# DC_DC_4V.net
KiCad netlist of a schematic drawn in Altium Designer
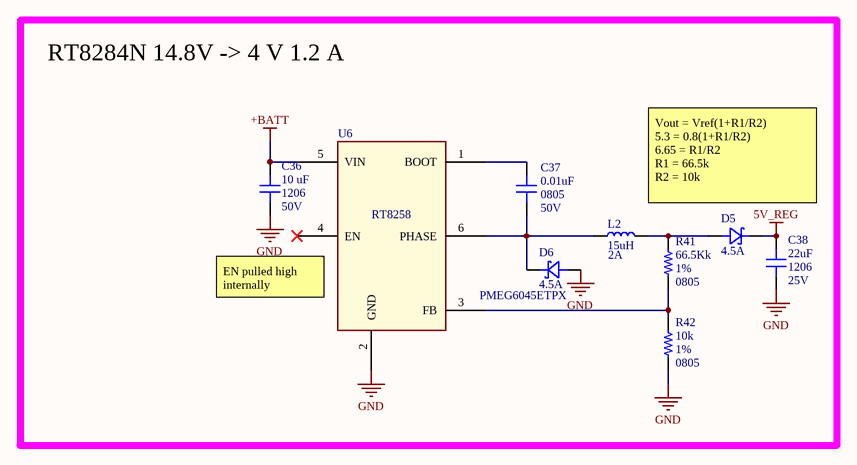
[diagram p0: DC_DC_4V.SchDoc]

(export (version "E")
  (design (tool "Eeschema 10.0.6"))
  (components
    (comp (ref "C36")
      (value "10 uF")
      (footprint "CAP_1206")
      (description "CAP - 1206")
      (fields
        (field (name "PACKAGE") "1206")
        (field (name "VOLTAGE") "50V")
        (field (name "PART NUMBER") "GRT31CR61H106ME01L")
      )
      (libsource (lib "SecureBot") (part "CAP - 1206"))
    )
    (comp (ref "C37")
      (value "0.01uF")
      (footprint "CAP_0805")
      (description "CAP - 0805")
      (fields
        (field (name "PART NUMBER") "CL21B103KBANNNC")
        (field (name "PACKAGE") "0805")
        (field (name "VOLTAGE") "50V")
      )
      (libsource (lib "SecureBot") (part "CAP - 0805"))
    )
    (comp (ref "C38")
      (value "22uF")
      (footprint "CAP_1206")
      (description "CAP - 1206")
      (fields
        (field (name "PART NUMBER") "CL31A226KAHNNNE")
        (field (name "PACKAGE") "1206")
        (field (name "VOLTAGE") "25V")
      )
      (libsource (lib "SecureBot") (part "CAP - 1206"))
    )
    (comp (ref "D5")
      (value "SCHOTTKEY")
      (footprint "DO-214AC_SOD128")
      (fields (field (name "CURRENT") "4.5A") (field (name "PART NUMBER") "PMEG6045ETPX"))
      (libsource (lib "SecureBot") (part "SCHOTTKEY"))
    )
    (comp (ref "D6")
      (value "SCHOTTKEY")
      (footprint "DO-214AC_SOD128")
      (fields (field (name "CURRENT") "4.5A") (field (name "PART NUMBER") "PMEG6045ETPX"))
      (libsource (lib "SecureBot") (part "SCHOTTKEY"))
    )
    (comp (ref "L2")
      (value "15uH")
      (footprint "NR5040T150M")
      (description "IND")
      (fields (field (name "CURRENT") "2A") (field (name "PART NUMBER") "NR5040T150M"))
      (libsource (lib "SecureBot") (part "IND"))
    )
    (comp (ref "R41")
      (value "66.5Kk")
      (footprint "FER_0805")
      (description "RES - 0805")
      (fields
        (field (name "TOLERANCE") "1%")
        (field (name "PACKAGE") "0805")
        (field (name "PART NUMBER") "RC0805FR-0766K5L")
      )
      (libsource (lib "SecureBot") (part "RES - 0805"))
    )
    (comp (ref "R42")
      (value "10k")
      (footprint "FER_0805")
      (description "RES - 0805")
      (fields
        (field (name "TOLERANCE") "1%")
        (field (name "PACKAGE") "0805")
        (field (name "PART NUMBER") "RMCF0805FT10K0")
      )
      (libsource (lib "SecureBot") (part "RES - 0805"))
    )
    (comp (ref "U6") (value "RT8258") (footprint "SOT23-6") (libsource (lib "SecureBot") (part "RT8258")))
  )
  (nets
    (net (code "1") (name "+BATT") (class "Default")
      (node (ref "C36") (pin "1") (pinfunction "1_1") (pintype "passive"))
      (node (ref "U6") (pin "5") (pinfunction "VIN_5") (pintype "passive"))
    )
    (net (code "2") (name "5V_REG") (class "Default")
      (node (ref "C38") (pin "1") (pinfunction "1_1") (pintype "passive"))
      (node (ref "D5") (pin "2") (pinfunction "2_2") (pintype "passive"))
    )
    (net (code "3") (name "GND") (class "Default")
      (node (ref "C36") (pin "2") (pinfunction "2_2") (pintype "passive"))
      (node (ref "C38") (pin "2") (pinfunction "2_2") (pintype "passive"))
      (node (ref "D6") (pin "1") (pinfunction "1_1") (pintype "passive"))
      (node (ref "R42") (pin "2") (pinfunction "2_2") (pintype "passive"))
      (node (ref "U6") (pin "2") (pinfunction "GND_2") (pintype "passive"))
    )
    (net (code "4") (name "Net-(D5-Pad1)") (class "Default")
      (node (ref "D5") (pin "1") (pinfunction "1_1") (pintype "passive"))
      (node (ref "L2") (pin "2") (pinfunction "2_2") (pintype "passive"))
      (node (ref "R41") (pin "1") (pinfunction "1_1") (pintype "passive"))
    )
    (net (code "5") (name "Net-(U6-BOOT)") (class "Default")
      (node (ref "C37") (pin "1") (pinfunction "1_1") (pintype "passive"))
      (node (ref "U6") (pin "1") (pinfunction "BOOT_1") (pintype "passive"))
    )
    (net (code "6") (name "Net-(U6-FB)") (class "Default")
      (node (ref "R41") (pin "2") (pinfunction "2_2") (pintype "passive"))
      (node (ref "R42") (pin "1") (pinfunction "1_1") (pintype "passive"))
      (node (ref "U6") (pin "3") (pinfunction "FB_3") (pintype "passive"))
    )
    (net (code "7") (name "Net-(U6-PHASE)") (class "Default")
      (node (ref "C37") (pin "2") (pinfunction "2_2") (pintype "passive"))
      (node (ref "D6") (pin "2") (pinfunction "2_2") (pintype "passive"))
      (node (ref "L2") (pin "1") (pinfunction "1_1") (pintype "passive"))
      (node (ref "U6") (pin "6") (pinfunction "PHASE_6") (pintype "passive"))
    )
    (net (code "8") (name "unconnected-(U6-EN-Pad4)") (class "Default")
      (node (ref "U6") (pin "4") (pinfunction "EN_4") (pintype "passive+no_connect"))
    )
  )
)
